# LT8315.net
KiCad netlist of a schematic drawn in Altium Designer
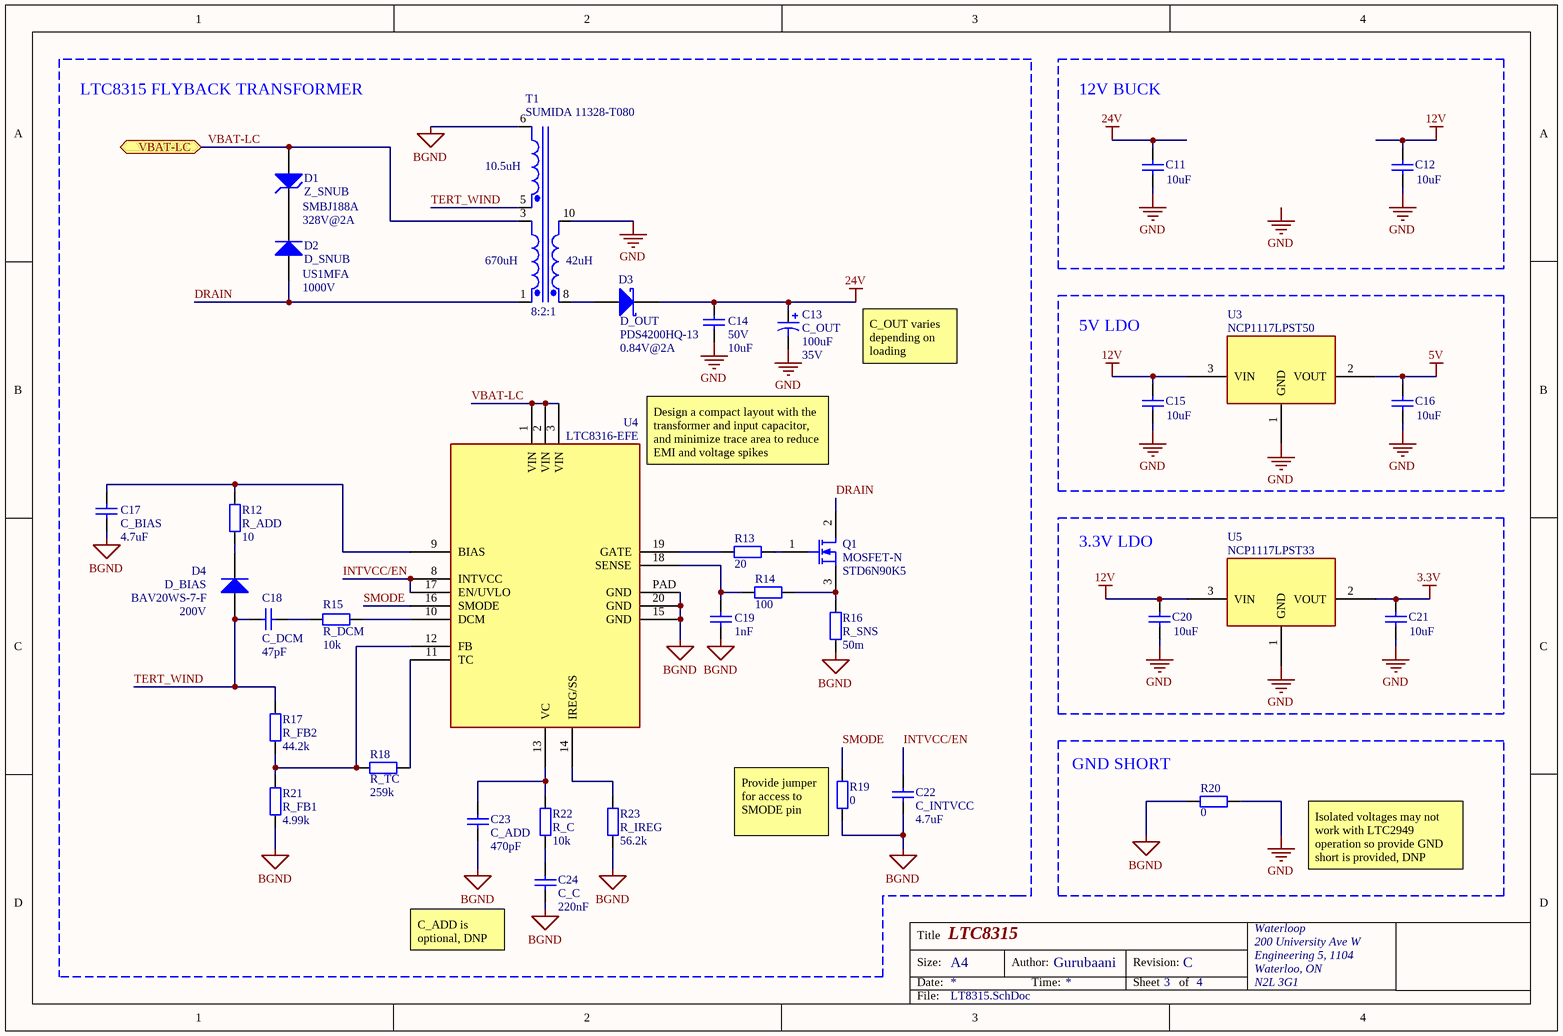
[diagram p0: LT8315.SchDoc]

(export (version "E")
  (design (tool "Eeschema 10.0.6"))
  (components
    (comp (ref "C11")
      (value "10uF")
      (footprint "Miscellaneous Devices:C0805")
      (description "Capacitor")
      (fields (field (name "Comment") "C_OUT") (field (name "PUBLISHER") "Altium Limited"))
      (libsource (lib "Miscellaneous Devices") (part "Cap"))
    )
    (comp (ref "C12")
      (value "10uF")
      (footprint "Miscellaneous Devices:C0805")
      (description "Capacitor")
      (fields (field (name "Comment") "C_OUT") (field (name "PUBLISHER") "Altium Limited"))
      (libsource (lib "Miscellaneous Devices") (part "Cap"))
    )
    (comp (ref "C13")
      (value "C_OUT")
      (footprint "RB7.6-15")
      (description "Polarized Capacitor (Radial)")
      (fields
        (field (name "ALTIUM_VALUE") "100uF")
        (field (name "VOLTAGE") "35V")
        (field (name "PUBLISHER") "Altium Limited")
      )
      (libsource (lib "Miscellaneous Devices") (part "Cap Pol1"))
    )
    (comp (ref "C14")
      (value "10uF")
      (footprint "Miscellaneous Devices:C0805")
      (description "Capacitor")
      (fields
        (field (name "VOLTAGE") "50V")
        (field (name "Comment") "C_OUT")
        (field (name "PUBLISHER") "Altium Limited")
      )
      (libsource (lib "Miscellaneous Devices") (part "Cap"))
    )
    (comp (ref "C15")
      (value "10uF")
      (footprint "Miscellaneous Devices:C0805")
      (description "Capacitor")
      (fields (field (name "Comment") "C_OUT") (field (name "PUBLISHER") "Altium Limited"))
      (libsource (lib "Miscellaneous Devices") (part "Cap"))
    )
    (comp (ref "C16")
      (value "10uF")
      (footprint "Miscellaneous Devices:C0805")
      (description "Capacitor")
      (fields (field (name "Comment") "C_OUT") (field (name "PUBLISHER") "Altium Limited"))
      (libsource (lib "Miscellaneous Devices") (part "Cap"))
    )
    (comp (ref "C17")
      (value "C_BIAS")
      (footprint "Miscellaneous Devices:C0805")
      (description "Capacitor")
      (fields (field (name "ALTIUM_VALUE") "4.7uF") (field (name "PUBLISHER") "Altium Limited"))
      (libsource (lib "Miscellaneous Devices") (part "Cap"))
    )
    (comp (ref "C18")
      (value "C_DCM")
      (footprint "Miscellaneous Devices:C0805")
      (description "Capacitor")
      (fields (field (name "ALTIUM_VALUE") "47pF") (field (name "PUBLISHER") "Altium Limited"))
      (libsource (lib "Miscellaneous Devices") (part "Cap"))
    )
    (comp (ref "C19")
      (value "1nF")
      (footprint "Miscellaneous Devices:C0805")
      (description "Capacitor")
      (fields (field (name "Comment") "C_OUT") (field (name "PUBLISHER") "Altium Limited"))
      (libsource (lib "Miscellaneous Devices") (part "Cap"))
    )
    (comp (ref "C20")
      (value "10uF")
      (footprint "Miscellaneous Devices:C0805")
      (description "Capacitor")
      (fields (field (name "Comment") "C_OUT") (field (name "PUBLISHER") "Altium Limited"))
      (libsource (lib "Miscellaneous Devices") (part "Cap"))
    )
    (comp (ref "C21")
      (value "10uF")
      (footprint "Miscellaneous Devices:C0805")
      (description "Capacitor")
      (fields (field (name "Comment") "C_OUT") (field (name "PUBLISHER") "Altium Limited"))
      (libsource (lib "Miscellaneous Devices") (part "Cap"))
    )
    (comp (ref "C22")
      (value "C_INTVCC")
      (footprint "Miscellaneous Devices:C0805")
      (description "Capacitor")
      (fields (field (name "ALTIUM_VALUE") "4.7uF") (field (name "PUBLISHER") "Altium Limited"))
      (libsource (lib "Miscellaneous Devices") (part "Cap"))
    )
    (comp (ref "C23")
      (value "C_ADD")
      (footprint "Miscellaneous Devices:C0805")
      (description "Capacitor")
      (fields (field (name "ALTIUM_VALUE") "470pF") (field (name "PUBLISHER") "Altium Limited"))
      (libsource (lib "Miscellaneous Devices") (part "Cap"))
    )
    (comp (ref "C24")
      (value "C_C")
      (footprint "Miscellaneous Devices:C0805")
      (description "Capacitor")
      (fields (field (name "ALTIUM_VALUE") "220nF") (field (name "PUBLISHER") "Altium Limited"))
      (libsource (lib "Miscellaneous Devices") (part "Cap"))
    )
    (comp (ref "D1")
      (value "Z_SNUB")
      (footprint "DO-214AA, SMB")
      (description "Zener Diode")
      (fields (field (name "REVERSE VOLTAGE") "328V@2A") (field (name "PARTNUMBER") "SMBJ188A"))
      (libsource (lib "Miscellaneous Devices") (part "D Zener"))
    )
    (comp (ref "D2")
      (value "D_SNUB")
      (footprint "SOD-123FL")
      (description "Default Diode")
      (fields (field (name "REVERSE VOLTAGE") "1000V") (field (name "PARTNUMBER") "US1MFA"))
      (libsource (lib "Miscellaneous Devices") (part "Diode"))
    )
    (comp (ref "D3")
      (value "D_OUT")
      (footprint "POWERDI5 (DPAK184P650X115-3N)")
      (description "Schottky Diode")
      (fields (field (name "FORWARD VOLTAGE") "0.84V@2A") (field (name "PARTNUMBER") "PDS4200HQ-13"))
      (libsource (lib "Miscellaneous Devices") (part "D Schottky"))
    )
    (comp (ref "D4")
      (value "D_BIAS")
      (footprint "SOD323")
      (description "Default Diode")
      (fields (field (name "REVERSE VOLTAGE") "200V") (field (name "PARTNUMBER") "BAV20WS-7-F"))
      (libsource (lib "Miscellaneous Devices") (part "Diode"))
    )
    (comp (ref "Q1")
      (value "MOSFET-N")
      (footprint "DPAK (228P972X240-3N)")
      (description "N-Channel MOSFET")
      (fields (field (name "PART NUMBER") "STD6N90K5") (field (name "PUBLISHER") "Altium Limited"))
      (libsource (lib "Miscellaneous Devices") (part "MOSFET-N"))
    )
    (comp (ref "R12")
      (value "R_ADD")
      (footprint "Miscellaneous Devices:J1-0603")
      (description "Resistor")
      (fields (field (name "ALTIUM_VALUE") "10") (field (name "PUBLISHER") "Altium Limited"))
      (libsource (lib "Miscellaneous Devices") (part "Res2"))
    )
    (comp (ref "R13")
      (value "20")
      (footprint "Miscellaneous Devices:J1-0603")
      (description "Resistor")
      (fields (field (name "Comment") "R_SNS") (field (name "PUBLISHER") "Altium Limited"))
      (libsource (lib "") (part "Res2_3"))
    )
    (comp (ref "R14")
      (value "100")
      (footprint "Miscellaneous Devices:J1-0603")
      (description "Resistor")
      (fields (field (name "Comment") "R_SNS") (field (name "PUBLISHER") "Altium Limited"))
      (libsource (lib "") (part "Res2_3"))
    )
    (comp (ref "R15")
      (value "R_DCM")
      (footprint "Miscellaneous Devices:J1-0603")
      (description "Resistor")
      (fields (field (name "ALTIUM_VALUE") "10k") (field (name "PUBLISHER") "Altium Limited"))
      (libsource (lib "") (part "Res2_1"))
    )
    (comp (ref "R16")
      (value "R_SNS")
      (footprint "Miscellaneous Devices:J1-0603")
      (description "Resistor")
      (fields (field (name "ALTIUM_VALUE") "50m") (field (name "PUBLISHER") "Altium Limited"))
      (libsource (lib "Miscellaneous Devices") (part "Res2"))
    )
    (comp (ref "R17")
      (value "R_FB2")
      (footprint "Miscellaneous Devices:J1-0603")
      (description "Resistor")
      (fields (field (name "ALTIUM_VALUE") "44.2k") (field (name "PUBLISHER") "Altium Limited"))
      (libsource (lib "") (part "Res2_2"))
    )
    (comp (ref "R18")
      (value "R_TC")
      (footprint "Miscellaneous Devices:J1-0603")
      (description "Resistor")
      (fields (field (name "ALTIUM_VALUE") "259k") (field (name "PUBLISHER") "Altium Limited"))
      (libsource (lib "") (part "Res2_1"))
    )
    (comp (ref "R19")
      (value "0")
      (footprint "Miscellaneous Devices:J1-0603")
      (description "Resistor")
      (fields (field (name "Comment") "R_C") (field (name "PUBLISHER") "Altium Limited"))
      (libsource (lib "") (part "Res2_2"))
    )
    (comp (ref "R20")
      (value "0")
      (footprint "Miscellaneous Devices:J1-0603")
      (description "Resistor")
      (fields (field (name "Comment") "R_C") (field (name "PUBLISHER") "Altium Limited"))
      (libsource (lib "") (part "Res2_1"))
    )
    (comp (ref "R21")
      (value "R_FB1")
      (footprint "Miscellaneous Devices:J1-0603")
      (description "Resistor")
      (fields (field (name "ALTIUM_VALUE") "4.99k") (field (name "PUBLISHER") "Altium Limited"))
      (libsource (lib "") (part "Res2_2"))
    )
    (comp (ref "R22")
      (value "R_C")
      (footprint "Miscellaneous Devices:J1-0603")
      (description "Resistor")
      (fields (field (name "ALTIUM_VALUE") "10k") (field (name "PUBLISHER") "Altium Limited"))
      (libsource (lib "") (part "Res2_2"))
    )
    (comp (ref "R23")
      (value "R_IREG")
      (footprint "Miscellaneous Devices:J1-0603")
      (description "Resistor")
      (fields (field (name "ALTIUM_VALUE") "56.2k") (field (name "PUBLISHER") "Altium Limited"))
      (libsource (lib "") (part "Res2_2"))
    )
    (comp (ref "T1")
      (value "8:2:1")
      (footprint "PQ2620")
      (description "Three-winding Transformer (Non-Ideal)")
      (fields
        (field (name "PART NUMBER") "SUMIDA 11328-T080")
        (field (name "PRIMARY INDUCTANCE") "670uH")
        (field (name "SECONDARY INDUCTANCE") "42uH")
        (field (name "TERTIARY INDUCATANCE") "10.5uH")
      )
      (libsource (lib "Miscellaneous Devices") (part "Trans3"))
    )
    (comp (ref "U3")
      (value "NCP1117LPST50")
      (footprint "NCP1117LPST")
      (description "IC REG LINEAR 5V 1A SOT223")
      (libsource (lib "LTC8315") (part "NCP1117LPST50"))
    )
    (comp (ref "U4")
      (value "LTC8316-EFE")
      (footprint "LTC8315/8316")
      (description "600VIN MICROPOWER, ISOLATED NO-O")
      (libsource (lib "LTC8315") (part "LTC8316-EFE"))
    )
    (comp (ref "U5")
      (value "NCP1117LPST33")
      (footprint "NCP1117LPST")
      (description "IC REG LINEAR 3.3V 1A SOT223")
      (libsource (lib "LTC8315") (part "NCP1117LPST33"))
    )
  )
  (nets
    (net (code "1") (name "/DRAIN") (class "Default")
      (node (ref "D2") (pin "1") (pinfunction "A_1") (pintype "passive"))
      (node (ref "Q1") (pin "2") (pinfunction "D_2") (pintype "passive"))
      (node (ref "T1") (pin "1") (pinfunction "Sec1+_1") (pintype "passive"))
    )
    (net (code "2") (name "/INTVCC{slash}EN") (class "Default")
      (node (ref "C22") (pin "1") (pinfunction "1_1") (pintype "passive"))
      (node (ref "U4") (pin "17") (pinfunction "EN/UVLO_17") (pintype "passive"))
      (node (ref "U4") (pin "8") (pinfunction "INTVCC_8") (pintype "passive"))
    )
    (net (code "3") (name "/SMODE") (class "Default")
      (node (ref "R19") (pin "2") (pinfunction "2_2") (pintype "passive"))
      (node (ref "U4") (pin "16") (pinfunction "SMODE_16") (pintype "passive"))
    )
    (net (code "4") (name "/TERT_WIND") (class "Default")
      (node (ref "C18") (pin "1") (pinfunction "1_1") (pintype "passive"))
      (node (ref "D4") (pin "1") (pinfunction "A_1") (pintype "passive"))
      (node (ref "R17") (pin "2") (pinfunction "2_2") (pintype "passive"))
      (node (ref "T1") (pin "5") (pinfunction "Sec2+_5") (pintype "passive"))
    )
    (net (code "5") (name "/VBAT-LC") (class "Default")
      (node (ref "D1") (pin "1") (pinfunction "A_1") (pintype "passive"))
      (node (ref "T1") (pin "3") (pinfunction "Sec1-_3") (pintype "passive"))
      (node (ref "U4") (pin "1") (pinfunction "VIN_1") (pintype "passive"))
      (node (ref "U4") (pin "2") (pinfunction "VIN_2") (pintype "passive"))
      (node (ref "U4") (pin "3") (pinfunction "VIN_3") (pintype "passive"))
    )
    (net (code "6") (name "3.3V") (class "Default")
      (node (ref "C21") (pin "2") (pinfunction "2_2") (pintype "passive"))
      (node (ref "U5") (pin "2") (pinfunction "VOUT_2") (pintype "passive"))
    )
    (net (code "7") (name "5V") (class "Default")
      (node (ref "C16") (pin "2") (pinfunction "2_2") (pintype "passive"))
      (node (ref "U3") (pin "2") (pinfunction "VOUT_2") (pintype "passive"))
    )
    (net (code "8") (name "12V") (class "Default")
      (node (ref "C12") (pin "2") (pinfunction "2_2") (pintype "passive"))
      (node (ref "C15") (pin "2") (pinfunction "2_2") (pintype "passive"))
      (node (ref "C20") (pin "2") (pinfunction "2_2") (pintype "passive"))
      (node (ref "U3") (pin "3") (pinfunction "VIN_3") (pintype "passive"))
      (node (ref "U5") (pin "3") (pinfunction "VIN_3") (pintype "passive"))
    )
    (net (code "9") (name "24V") (class "Default")
      (node (ref "C11") (pin "2") (pinfunction "2_2") (pintype "passive"))
      (node (ref "C13") (pin "1") (pinfunction "1_1") (pintype "passive"))
      (node (ref "C14") (pin "2") (pinfunction "2_2") (pintype "passive"))
      (node (ref "D3") (pin "2") (pinfunction "K_2") (pintype "passive"))
    )
    (net (code "10") (name "BGND") (class "Default")
      (node (ref "C17") (pin "1") (pinfunction "1_1") (pintype "passive"))
      (node (ref "C19") (pin "1") (pinfunction "1_1") (pintype "passive"))
      (node (ref "C22") (pin "2") (pinfunction "2_2") (pintype "passive"))
      (node (ref "C23") (pin "1") (pinfunction "1_1") (pintype "passive"))
      (node (ref "C24") (pin "1") (pinfunction "1_1") (pintype "passive"))
      (node (ref "R16") (pin "2") (pinfunction "2_2") (pintype "passive"))
      (node (ref "R19") (pin "1") (pinfunction "1_1") (pintype "passive"))
      (node (ref "R20") (pin "2") (pinfunction "2_2") (pintype "passive"))
      (node (ref "R21") (pin "1") (pinfunction "1_1") (pintype "passive"))
      (node (ref "R23") (pin "1") (pinfunction "1_1") (pintype "passive"))
      (node (ref "T1") (pin "6") (pinfunction "Sec2-_6") (pintype "passive"))
      (node (ref "U4") (pin "15") (pinfunction "GND_15") (pintype "passive"))
      (node (ref "U4") (pin "20") (pinfunction "GND_20") (pintype "passive"))
      (node (ref "U4") (pin "PAD") (pinfunction "GND_PAD") (pintype "passive"))
    )
    (net (code "11") (name "GND") (class "Default")
      (node (ref "C11") (pin "1") (pinfunction "1_1") (pintype "passive"))
      (node (ref "C12") (pin "1") (pinfunction "1_1") (pintype "passive"))
      (node (ref "C13") (pin "2") (pinfunction "2_2") (pintype "passive"))
      (node (ref "C14") (pin "1") (pinfunction "1_1") (pintype "passive"))
      (node (ref "C15") (pin "1") (pinfunction "1_1") (pintype "passive"))
      (node (ref "C16") (pin "1") (pinfunction "1_1") (pintype "passive"))
      (node (ref "C20") (pin "1") (pinfunction "1_1") (pintype "passive"))
      (node (ref "C21") (pin "1") (pinfunction "1_1") (pintype "passive"))
      (node (ref "R20") (pin "1") (pinfunction "1_1") (pintype "passive"))
      (node (ref "T1") (pin "10") (pinfunction "Pri-_10") (pintype "passive"))
      (node (ref "U3") (pin "1") (pinfunction "GND_1") (pintype "passive"))
      (node (ref "U5") (pin "1") (pinfunction "GND_1") (pintype "passive"))
    )
    (net (code "12") (name "Net-(C18-Pad2)") (class "Default")
      (node (ref "C18") (pin "2") (pinfunction "2_2") (pintype "passive"))
      (node (ref "R15") (pin "2") (pinfunction "2_2") (pintype "passive"))
    )
    (net (code "13") (name "Net-(C24-Pad2)") (class "Default")
      (node (ref "C24") (pin "2") (pinfunction "2_2") (pintype "passive"))
      (node (ref "R22") (pin "1") (pinfunction "1_1") (pintype "passive"))
    )
    (net (code "14") (name "Net-(D1-K)") (class "Default")
      (node (ref "D1") (pin "2") (pinfunction "K_2") (pintype "passive"))
      (node (ref "D2") (pin "2") (pinfunction "K_2") (pintype "passive"))
    )
    (net (code "15") (name "Net-(D3-A)") (class "Default")
      (node (ref "D3") (pin "1") (pinfunction "A_1") (pintype "passive"))
      (node (ref "T1") (pin "8") (pinfunction "Pri+_8") (pintype "passive"))
    )
    (net (code "16") (name "Net-(D4-K)") (class "Default")
      (node (ref "D4") (pin "2") (pinfunction "K_2") (pintype "passive"))
      (node (ref "R12") (pin "2") (pinfunction "2_2") (pintype "passive"))
    )
    (net (code "17") (name "Net-(Q1-G)") (class "Default")
      (node (ref "Q1") (pin "1") (pinfunction "G_1") (pintype "passive"))
      (node (ref "R13") (pin "2") (pinfunction "2_2") (pintype "passive"))
    )
    (net (code "18") (name "Net-(Q1-S)") (class "Default")
      (node (ref "Q1") (pin "3") (pinfunction "S_3") (pintype "passive"))
      (node (ref "R14") (pin "2") (pinfunction "2_2") (pintype "passive"))
      (node (ref "R16") (pin "1") (pinfunction "1_1") (pintype "passive"))
    )
    (net (code "19") (name "Net-(U4-BIAS)") (class "Default")
      (node (ref "C17") (pin "2") (pinfunction "2_2") (pintype "passive"))
      (node (ref "R12") (pin "1") (pinfunction "1_1") (pintype "passive"))
      (node (ref "U4") (pin "9") (pinfunction "BIAS_9") (pintype "passive"))
    )
    (net (code "20") (name "Net-(U4-DCM)") (class "Default")
      (node (ref "R15") (pin "1") (pinfunction "1_1") (pintype "passive"))
      (node (ref "U4") (pin "10") (pinfunction "DCM_10") (pintype "passive"))
    )
    (net (code "21") (name "Net-(U4-FB)") (class "Default")
      (node (ref "R17") (pin "1") (pinfunction "1_1") (pintype "passive"))
      (node (ref "R18") (pin "2") (pinfunction "2_2") (pintype "passive"))
      (node (ref "R21") (pin "2") (pinfunction "2_2") (pintype "passive"))
      (node (ref "U4") (pin "12") (pinfunction "FB_12") (pintype "passive"))
    )
    (net (code "22") (name "Net-(U4-GATE)") (class "Default")
      (node (ref "R13") (pin "1") (pinfunction "1_1") (pintype "passive"))
      (node (ref "U4") (pin "19") (pinfunction "GATE_19") (pintype "passive"))
    )
    (net (code "23") (name "Net-(U4-IREG{slash}SS)") (class "Default")
      (node (ref "R23") (pin "2") (pinfunction "2_2") (pintype "passive"))
      (node (ref "U4") (pin "14") (pinfunction "IREG/SS_14") (pintype "passive"))
    )
    (net (code "24") (name "Net-(U4-SENSE)") (class "Default")
      (node (ref "C19") (pin "2") (pinfunction "2_2") (pintype "passive"))
      (node (ref "R14") (pin "1") (pinfunction "1_1") (pintype "passive"))
      (node (ref "U4") (pin "18") (pinfunction "SENSE_18") (pintype "passive"))
    )
    (net (code "25") (name "Net-(U4-TC)") (class "Default")
      (node (ref "R18") (pin "1") (pinfunction "1_1") (pintype "passive"))
      (node (ref "U4") (pin "11") (pinfunction "TC_11") (pintype "passive"))
    )
    (net (code "26") (name "Net-(U4-VC)") (class "Default")
      (node (ref "C23") (pin "2") (pinfunction "2_2") (pintype "passive"))
      (node (ref "R22") (pin "2") (pinfunction "2_2") (pintype "passive"))
      (node (ref "U4") (pin "13") (pinfunction "VC_13") (pintype "passive"))
    )
  )
)
